# PrimalLogger_Feather_TalonPlug.net
KiCad netlist of a schematic drawn in EAGLE
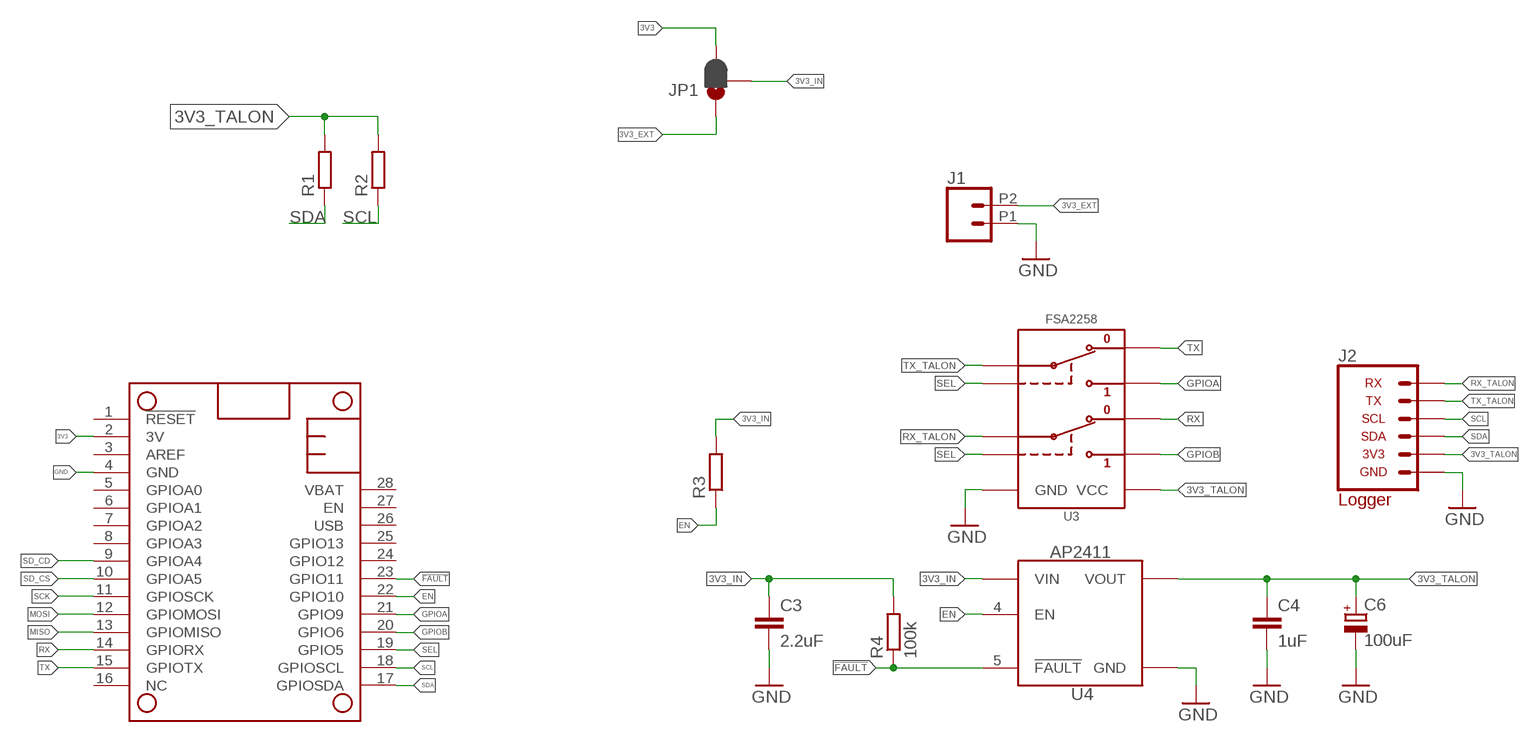
[diagram p0: schematic, sheet 1]

(export (version "E")
  (design (tool "Eeschema 10.0.6"))
  (components
    (comp (ref "C3")
      (value "2.2uF")
      (footprint "eagle-import:C0603")
      (fields (field (name "MF") "Samsung") (field (name "MPN") "CL10A225KQ8NNNC"))
      (libsource (lib "eagle-import") (part "C-EUC06032.2UF"))
    )
    (comp (ref "C4")
      (value "1uF")
      (footprint "eagle-import:C0603")
      (fields (field (name "MF") "Yaiyo Yuden") (field (name "MPN") "EMK107BJ105KA-T"))
      (libsource (lib "eagle-import") (part "C-EUC06031UF"))
    )
    (comp (ref "C6")
      (value "100uF")
      (footprint "eagle-import:C1411_TANT")
      (fields (field (name "MF") "Kyocera AVX") (field (name "MPN") "TPSB107M010R0400"))
      (libsource (lib "eagle-import") (part "CTANT_EU1411"))
    )
    (comp (ref "J1")
      (value "CONN_022.54_SCREW_ROUND")
      (footprint "eagle-import:1X02_2.54_SCREWTERM_ROUND")
      (fields (field (name "MF") "OnShore") (field (name "MPN") "OSTVN02A150"))
      (libsource (lib "eagle-import") (part "CONN_022.54_SCREW_ROUND"))
    )
    (comp (ref "J2")
      (value "CONN_TALON_LOGGER")
      (footprint "eagle-import:1X06_MICROLOCKPLUS_RT")
      (fields (field (name "DISP") "Logger") (field (name "MF") "Molex") (field (name "MPN") "5055670681"))
      (libsource (lib "eagle-import") (part "CONN_TALON_LOGGER"))
    )
    (comp (ref "JP1")
      (value "JUMPER-SMT_3_1-NC_PASTE_SILK")
      (footprint "eagle-import:SMT-JUMPER_3_1-NC_PASTE_SILK")
      (libsource (lib "eagle-import") (part "JUMPER-SMT_3_1-NC_PASTE_SILK"))
    )
    (comp (ref "MS1")
      (value "FEATHERWING_NODIM")
      (footprint "eagle-import:FEATHERWING_DIM")
      (libsource (lib "eagle-import") (part "FEATHERWING_NODIM"))
    )
    (comp (ref "R1")
      (value "R-EU_10KR0603")
      (footprint "eagle-import:R0603")
      (fields
        (field (name "MF") "Yageo")
        (field (name "MPN") "RC0603FR-0710KL")
        (field (name "VALUE_PART") "10k")
      )
      (libsource (lib "eagle-import") (part "R-EU_R060310K"))
    )
    (comp (ref "R2")
      (value "R-EU_10KR0603")
      (footprint "eagle-import:R0603")
      (fields
        (field (name "MF") "Yageo")
        (field (name "MPN") "RC0603FR-0710KL")
        (field (name "VALUE_PART") "10k")
      )
      (libsource (lib "eagle-import") (part "R-EU_R060310K"))
    )
    (comp (ref "R3")
      (value "R-EU_100KR0603")
      (footprint "eagle-import:R0603")
      (fields
        (field (name "MF") "Yageo")
        (field (name "MPN") "RC0603FR-07100KL")
        (field (name "VALUE_PART") "100k")
      )
      (libsource (lib "eagle-import") (part "R-EU_R0603100K"))
    )
    (comp (ref "R4")
      (value "100k")
      (footprint "eagle-import:R0603")
      (fields (field (name "MF") "Yageo") (field (name "MPN") "RC0603FR-07100KL"))
      (libsource (lib "eagle-import") (part "R-EU_R0603100K"))
    )
    (comp (ref "U3")
      (value "FSA2258")
      (footprint "eagle-import:MICROPAK_10")
      (fields (field (name "DISP") "FSA2258") (field (name "MF") "OnSemi") (field (name "MPN") "FSA2258L10X"))
      (libsource (lib "eagle-import") (part "FSA2258"))
    )
    (comp (ref "U4")
      (value "AP2411")
      (footprint "eagle-import:MSOP_8EP")
      (fields
        (field (name "DISP") "AP2411")
        (field (name "MF") "Diodes Inc")
        (field (name "MPN") "AP2411MP-13")
      )
      (libsource (lib "eagle-import") (part "AP2411"))
    )
  )
  (nets
    (net (code "1") (name "/USB") (class "Default")
      (node (ref "MS1") (pin "26") (pinfunction "USB_26") (pintype "power_in"))
    )
    (net (code "2") (name "/VBAT") (class "Default")
      (node (ref "MS1") (pin "28") (pinfunction "VBAT_28") (pintype "power_in"))
    )
    (net (code "3") (name "/~{FAULT}") (class "Default")
      (node (ref "MS1") (pin "23") (pinfunction "GPIO11_23") (pintype "bidirectional"))
      (node (ref "R4") (pin "1") (pinfunction "1_1") (pintype "passive"))
      (node (ref "U4") (pin "5") (pinfunction "~{FAULT}_5") (pintype "output"))
    )
    (net (code "4") (name "3V3") (class "Default")
      (node (ref "JP1") (pin "3") (pinfunction "3_3") (pintype "passive"))
      (node (ref "MS1") (pin "2") (pinfunction "3V_2") (pintype "power_in"))
    )
    (net (code "5") (name "3V3_EXT") (class "Default")
      (node (ref "J1") (pin "P2") (pinfunction "2_P2") (pintype "passive"))
      (node (ref "JP1") (pin "1") (pinfunction "1_1") (pintype "passive"))
    )
    (net (code "6") (name "3V3_IN") (class "Default")
      (node (ref "C3") (pin "1") (pinfunction "1_1") (pintype "passive"))
      (node (ref "JP1") (pin "2") (pinfunction "2_2") (pintype "passive"))
      (node (ref "R3") (pin "2") (pinfunction "2_2") (pintype "passive"))
      (node (ref "R4") (pin "2") (pinfunction "2_2") (pintype "passive"))
      (node (ref "U4") (pin "2") (pinfunction "VIN_2") (pintype "power_in"))
      (node (ref "U4") (pin "3") (pinfunction "VIN_3") (pintype "power_in"))
    )
    (net (code "7") (name "3V3_TALON") (class "Default")
      (node (ref "C4") (pin "1") (pinfunction "1_1") (pintype "passive"))
      (node (ref "C6") (pin "ANODE") (pinfunction "+_ANODE") (pintype "passive"))
      (node (ref "J2") (pin "2") (pinfunction "3V3_2") (pintype "passive"))
      (node (ref "R1") (pin "2") (pinfunction "2_2") (pintype "passive"))
      (node (ref "R2") (pin "2") (pinfunction "2_2") (pintype "passive"))
      (node (ref "U3") (pin "10") (pinfunction "VCC_10") (pintype "power_in"))
      (node (ref "U4") (pin "6") (pinfunction "VOUT_6") (pintype "power_in"))
      (node (ref "U4") (pin "7") (pinfunction "VOUT_7") (pintype "power_in"))
    )
    (net (code "8") (name "EN") (class "Default")
      (node (ref "MS1") (pin "22") (pinfunction "GPIO10_22") (pintype "bidirectional"))
      (node (ref "R3") (pin "1") (pinfunction "1_1") (pintype "passive"))
      (node (ref "U4") (pin "4") (pinfunction "EN_4") (pintype "input"))
    )
    (net (code "9") (name "GND") (class "Default")
      (node (ref "C3") (pin "2") (pinfunction "2_2") (pintype "passive"))
      (node (ref "C4") (pin "2") (pinfunction "2_2") (pintype "passive"))
      (node (ref "C6") (pin "CATHODE") (pinfunction "-_CATHODE") (pintype "passive"))
      (node (ref "J1") (pin "P1") (pinfunction "1_P1") (pintype "passive"))
      (node (ref "J2") (pin "1") (pinfunction "GND_1") (pintype "passive"))
      (node (ref "MS1") (pin "4") (pinfunction "GND_4") (pintype "power_in"))
      (node (ref "U3") (pin "5") (pinfunction "GND_5") (pintype "power_in"))
      (node (ref "U4") (pin "1") (pinfunction "GND_1") (pintype "power_in"))
      (node (ref "U4") (pin "EP") (pinfunction "GND_EP") (pintype "power_in"))
    )
    (net (code "10") (name "GPIOA") (class "Default")
      (node (ref "MS1") (pin "21") (pinfunction "GPIO9_21") (pintype "bidirectional"))
      (node (ref "U3") (pin "2") (pinfunction "1B1_2") (pintype "bidirectional"))
    )
    (net (code "11") (name "GPIOB") (class "Default")
      (node (ref "MS1") (pin "20") (pinfunction "GPIO6_20") (pintype "bidirectional"))
      (node (ref "U3") (pin "4") (pinfunction "2B1_4") (pintype "bidirectional"))
    )
    (net (code "12") (name "MISO") (class "Default")
      (node (ref "MS1") (pin "13") (pinfunction "GPIOMISO_13") (pintype "bidirectional"))
    )
    (net (code "13") (name "MOSI") (class "Default")
      (node (ref "MS1") (pin "12") (pinfunction "GPIOMOSI_12") (pintype "bidirectional"))
    )
    (net (code "14") (name "RX") (class "Default")
      (node (ref "MS1") (pin "14") (pinfunction "GPIORX_14") (pintype "bidirectional"))
      (node (ref "U3") (pin "3") (pinfunction "2B0_3") (pintype "bidirectional"))
    )
    (net (code "15") (name "RX_TALON") (class "Default")
      (node (ref "J2") (pin "6") (pinfunction "RX_6") (pintype "passive"))
      (node (ref "U3") (pin "6") (pinfunction "2A_6") (pintype "bidirectional"))
    )
    (net (code "16") (name "SCK") (class "Default")
      (node (ref "MS1") (pin "11") (pinfunction "GPIOSCK_11") (pintype "bidirectional"))
    )
    (net (code "17") (name "SCL") (class "Default")
      (node (ref "J2") (pin "4") (pinfunction "SCL_4") (pintype "passive"))
      (node (ref "MS1") (pin "18") (pinfunction "GPIOSCL_18") (pintype "bidirectional"))
      (node (ref "R2") (pin "1") (pinfunction "1_1") (pintype "passive"))
    )
    (net (code "18") (name "SDA") (class "Default")
      (node (ref "J2") (pin "3") (pinfunction "SDA_3") (pintype "passive"))
      (node (ref "MS1") (pin "17") (pinfunction "GPIOSDA_17") (pintype "bidirectional"))
      (node (ref "R1") (pin "1") (pinfunction "1_1") (pintype "passive"))
    )
    (net (code "19") (name "SD_CD") (class "Default")
      (node (ref "MS1") (pin "9") (pinfunction "GPIOA4_9") (pintype "bidirectional"))
    )
    (net (code "20") (name "SD_CS") (class "Default")
      (node (ref "MS1") (pin "10") (pinfunction "GPIOA5_10") (pintype "bidirectional"))
    )
    (net (code "21") (name "SEL") (class "Default")
      (node (ref "MS1") (pin "19") (pinfunction "GPIO5_19") (pintype "bidirectional"))
      (node (ref "U3") (pin "7") (pinfunction "S2_7") (pintype "input"))
      (node (ref "U3") (pin "8") (pinfunction "S1_8") (pintype "input"))
    )
    (net (code "22") (name "TX") (class "Default")
      (node (ref "MS1") (pin "15") (pinfunction "GPIOTX_15") (pintype "bidirectional"))
      (node (ref "U3") (pin "1") (pinfunction "1B0_1") (pintype "bidirectional"))
    )
    (net (code "23") (name "TX_TALON") (class "Default")
      (node (ref "J2") (pin "5") (pinfunction "TX_5") (pintype "passive"))
      (node (ref "U3") (pin "9") (pinfunction "1A_9") (pintype "bidirectional"))
    )
    (net (code "24") (name "unconnected-(MS1-AREF-Pad3)") (class "Default")
      (node (ref "MS1") (pin "3") (pinfunction "AREF_3") (pintype "passive"))
    )
    (net (code "25") (name "unconnected-(MS1-EN-Pad27)") (class "Default")
      (node (ref "MS1") (pin "27") (pinfunction "EN_27") (pintype "passive"))
    )
    (net (code "26") (name "unconnected-(MS1-GPIO12-Pad24)") (class "Default")
      (node (ref "MS1") (pin "24") (pinfunction "GPIO12_24") (pintype "bidirectional"))
    )
    (net (code "27") (name "unconnected-(MS1-GPIO13-Pad25)") (class "Default")
      (node (ref "MS1") (pin "25") (pinfunction "GPIO13_25") (pintype "bidirectional"))
    )
    (net (code "28") (name "unconnected-(MS1-GPIOA0-Pad5)") (class "Default")
      (node (ref "MS1") (pin "5") (pinfunction "GPIOA0_5") (pintype "bidirectional"))
    )
    (net (code "29") (name "unconnected-(MS1-GPIOA1-Pad6)") (class "Default")
      (node (ref "MS1") (pin "6") (pinfunction "GPIOA1_6") (pintype "bidirectional"))
    )
    (net (code "30") (name "unconnected-(MS1-GPIOA2-Pad7)") (class "Default")
      (node (ref "MS1") (pin "7") (pinfunction "GPIOA2_7") (pintype "bidirectional"))
    )
    (net (code "31") (name "unconnected-(MS1-GPIOA3-Pad8)") (class "Default")
      (node (ref "MS1") (pin "8") (pinfunction "GPIOA3_8") (pintype "bidirectional"))
    )
    (net (code "32") (name "unconnected-(MS1-NC-Pad16)") (class "Default")
      (node (ref "MS1") (pin "16") (pinfunction "NC_16") (pintype "passive"))
    )
    (net (code "33") (name "unconnected-(MS1-~{RESET}-Pad1)") (class "Default")
      (node (ref "MS1") (pin "1") (pinfunction "~{RESET}_1") (pintype "input"))
    )
  )
)
